# MaxBoard.net
KiCad netlist of a schematic drawn in EAGLE
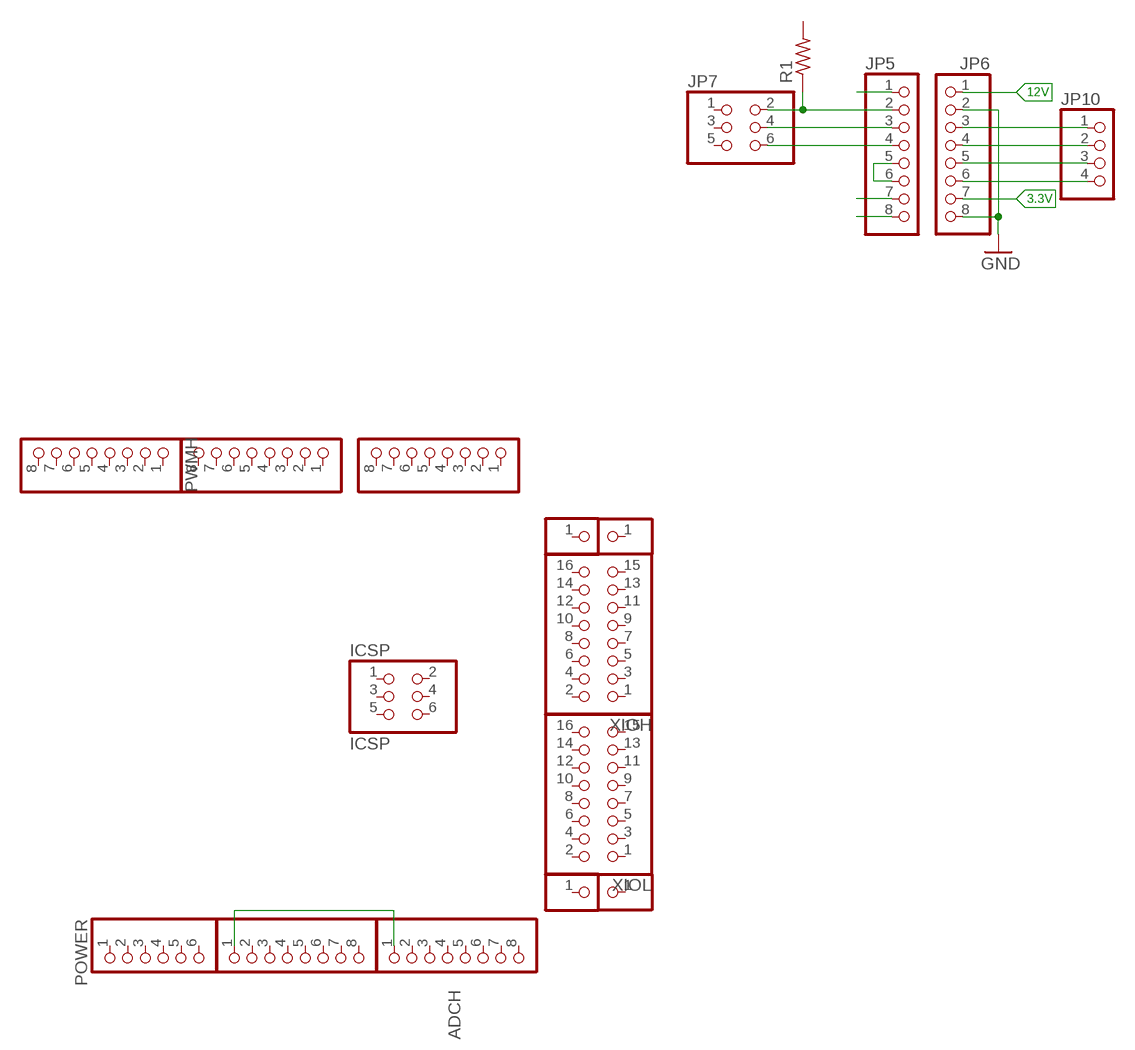
[diagram p0: schematic, sheet 1]

(export (version "E")
  (design (tool "Eeschema 10.0.6"))
  (components
    (comp (ref "ADCH")
      (value "PINHD-1X8")
      (footprint "eagle-import:1X08")
      (libsource (lib "eagle-import") (part "PINHD-1X8"))
    )
    (comp (ref "ADCL")
      (value "PINHD-1X8")
      (footprint "eagle-import:1X08")
      (libsource (lib "eagle-import") (part "PINHD-1X8"))
    )
    (comp (ref "COMMUNICATION")
      (value "PINHD-1X8")
      (footprint "eagle-import:1X08")
      (libsource (lib "eagle-import") (part "PINHD-1X8"))
    )
    (comp (ref "ICSP")
      (value "ICSP")
      (footprint "eagle-import:2X03")
      (libsource (lib "eagle-import") (part "PINHD-2X3"))
    )
    (comp (ref "JP1")
      (value "PINHD-1X1")
      (footprint "eagle-import:1X01")
      (libsource (lib "eagle-import") (part "PINHD-1X1"))
    )
    (comp (ref "JP2")
      (value "PINHD-1X1")
      (footprint "eagle-import:1X01")
      (libsource (lib "eagle-import") (part "PINHD-1X1"))
    )
    (comp (ref "JP3")
      (value "PINHD-1X1")
      (footprint "eagle-import:1X01")
      (libsource (lib "eagle-import") (part "PINHD-1X1"))
    )
    (comp (ref "JP4")
      (value "PINHD-1X1")
      (footprint "eagle-import:1X01")
      (libsource (lib "eagle-import") (part "PINHD-1X1"))
    )
    (comp (ref "JP5")
      (value "PINHD-1X8")
      (footprint "eagle-import:1X08")
      (libsource (lib "eagle-import") (part "PINHD-1X8"))
    )
    (comp (ref "JP6")
      (value "PINHD-1X8")
      (footprint "eagle-import:1X08")
      (libsource (lib "eagle-import") (part "PINHD-1X8"))
    )
    (comp (ref "JP7")
      (value "PINHD-2X3")
      (footprint "eagle-import:2X03")
      (libsource (lib "eagle-import") (part "PINHD-2X3"))
    )
    (comp (ref "JP10")
      (value "PINHD-1X4")
      (footprint "eagle-import:1X04")
      (libsource (lib "eagle-import") (part "PINHD-1X4"))
    )
    (comp (ref "POWER")
      (value "PINHD-1X6")
      (footprint "eagle-import:1X06")
      (libsource (lib "eagle-import") (part "PINHD-1X6"))
    )
    (comp (ref "PWMH")
      (value "PINHD-1X8")
      (footprint "eagle-import:1X08")
      (libsource (lib "eagle-import") (part "PINHD-1X8"))
    )
    (comp (ref "PWML")
      (value "PINHD-1X8")
      (footprint "eagle-import:1X08")
      (libsource (lib "eagle-import") (part "PINHD-1X8"))
    )
    (comp (ref "R1")
      (value "R-US_0207/7")
      (footprint "eagle-import:0207_7")
      (libsource (lib "eagle-import") (part "R-US_0207/7"))
    )
    (comp (ref "XIOH")
      (value "PINHD-2X8")
      (footprint "eagle-import:2X08")
      (libsource (lib "eagle-import") (part "PINHD-2X8"))
    )
    (comp (ref "XIOL")
      (value "PINHD-2X8")
      (footprint "eagle-import:2X08")
      (libsource (lib "eagle-import") (part "PINHD-2X8"))
    )
  )
  (nets
    (net (code "1") (name "3.3V") (class "Default")
      (node (ref "JP6") (pin "7") (pinfunction "7_7") (pintype "passive"))
    )
    (net (code "2") (name "12V") (class "Default")
      (node (ref "JP6") (pin "1") (pinfunction "1_1") (pintype "passive"))
    )
    (net (code "3") (name "GND") (class "Default")
      (node (ref "JP6") (pin "2") (pinfunction "2_2") (pintype "passive"))
      (node (ref "JP6") (pin "8") (pinfunction "8_8") (pintype "passive"))
    )
    (net (code "4") (name "Net-(ADCH-Pad1)") (class "Default")
      (node (ref "ADCH") (pin "1") (pinfunction "1_1") (pintype "passive"))
      (node (ref "ADCL") (pin "1") (pinfunction "1_1") (pintype "passive"))
    )
    (net (code "5") (name "Net-(JP5-Pad2)") (class "Default")
      (node (ref "JP5") (pin "2") (pinfunction "2_2") (pintype "passive"))
      (node (ref "JP7") (pin "2") (pinfunction "2_2") (pintype "passive"))
      (node (ref "R1") (pin "1") (pinfunction "1_1") (pintype "passive"))
    )
    (net (code "6") (name "Net-(JP5-Pad3)") (class "Default")
      (node (ref "JP5") (pin "3") (pinfunction "3_3") (pintype "passive"))
      (node (ref "JP7") (pin "4") (pinfunction "4_4") (pintype "passive"))
    )
    (net (code "7") (name "Net-(JP5-Pad4)") (class "Default")
      (node (ref "JP5") (pin "4") (pinfunction "4_4") (pintype "passive"))
      (node (ref "JP7") (pin "6") (pinfunction "6_6") (pintype "passive"))
    )
    (net (code "8") (name "Net-(JP5-Pad5)") (class "Default")
      (node (ref "JP5") (pin "5") (pinfunction "5_5") (pintype "passive"))
      (node (ref "JP5") (pin "6") (pinfunction "6_6") (pintype "passive"))
    )
    (net (code "9") (name "Net-(JP10-Pad1)") (class "Default")
      (node (ref "JP10") (pin "1") (pinfunction "1_1") (pintype "passive"))
      (node (ref "JP6") (pin "3") (pinfunction "3_3") (pintype "passive"))
    )
    (net (code "10") (name "Net-(JP10-Pad2)") (class "Default")
      (node (ref "JP10") (pin "2") (pinfunction "2_2") (pintype "passive"))
      (node (ref "JP6") (pin "4") (pinfunction "4_4") (pintype "passive"))
    )
    (net (code "11") (name "Net-(JP10-Pad3)") (class "Default")
      (node (ref "JP10") (pin "3") (pinfunction "3_3") (pintype "passive"))
      (node (ref "JP6") (pin "5") (pinfunction "5_5") (pintype "passive"))
    )
    (net (code "12") (name "Net-(JP10-Pad4)") (class "Default")
      (node (ref "JP10") (pin "4") (pinfunction "4_4") (pintype "passive"))
      (node (ref "JP6") (pin "6") (pinfunction "6_6") (pintype "passive"))
    )
    (net (code "13") (name "unconnected-(ADCH-Pad2)") (class "Default")
      (node (ref "ADCH") (pin "2") (pinfunction "2_2") (pintype "passive"))
    )
    (net (code "14") (name "unconnected-(ADCH-Pad3)") (class "Default")
      (node (ref "ADCH") (pin "3") (pinfunction "3_3") (pintype "passive"))
    )
    (net (code "15") (name "unconnected-(ADCH-Pad4)") (class "Default")
      (node (ref "ADCH") (pin "4") (pinfunction "4_4") (pintype "passive"))
    )
    (net (code "16") (name "unconnected-(ADCH-Pad5)") (class "Default")
      (node (ref "ADCH") (pin "5") (pinfunction "5_5") (pintype "passive"))
    )
    (net (code "17") (name "unconnected-(ADCH-Pad6)") (class "Default")
      (node (ref "ADCH") (pin "6") (pinfunction "6_6") (pintype "passive"))
    )
    (net (code "18") (name "unconnected-(ADCH-Pad7)") (class "Default")
      (node (ref "ADCH") (pin "7") (pinfunction "7_7") (pintype "passive"))
    )
    (net (code "19") (name "unconnected-(ADCH-Pad8)") (class "Default")
      (node (ref "ADCH") (pin "8") (pinfunction "8_8") (pintype "passive"))
    )
    (net (code "20") (name "unconnected-(ADCL-Pad2)") (class "Default")
      (node (ref "ADCL") (pin "2") (pinfunction "2_2") (pintype "passive"))
    )
    (net (code "21") (name "unconnected-(ADCL-Pad3)") (class "Default")
      (node (ref "ADCL") (pin "3") (pinfunction "3_3") (pintype "passive"))
    )
    (net (code "22") (name "unconnected-(ADCL-Pad4)") (class "Default")
      (node (ref "ADCL") (pin "4") (pinfunction "4_4") (pintype "passive"))
    )
    (net (code "23") (name "unconnected-(ADCL-Pad5)") (class "Default")
      (node (ref "ADCL") (pin "5") (pinfunction "5_5") (pintype "passive"))
    )
    (net (code "24") (name "unconnected-(ADCL-Pad6)") (class "Default")
      (node (ref "ADCL") (pin "6") (pinfunction "6_6") (pintype "passive"))
    )
    (net (code "25") (name "unconnected-(ADCL-Pad7)") (class "Default")
      (node (ref "ADCL") (pin "7") (pinfunction "7_7") (pintype "passive"))
    )
    (net (code "26") (name "unconnected-(ADCL-Pad8)") (class "Default")
      (node (ref "ADCL") (pin "8") (pinfunction "8_8") (pintype "passive"))
    )
    (net (code "27") (name "unconnected-(COMMUNICATION-Pad1)") (class "Default")
      (node (ref "COMMUNICATION") (pin "1") (pinfunction "1_1") (pintype "passive"))
    )
    (net (code "28") (name "unconnected-(COMMUNICATION-Pad2)") (class "Default")
      (node (ref "COMMUNICATION") (pin "2") (pinfunction "2_2") (pintype "passive"))
    )
    (net (code "29") (name "unconnected-(COMMUNICATION-Pad3)") (class "Default")
      (node (ref "COMMUNICATION") (pin "3") (pinfunction "3_3") (pintype "passive"))
    )
    (net (code "30") (name "unconnected-(COMMUNICATION-Pad4)") (class "Default")
      (node (ref "COMMUNICATION") (pin "4") (pinfunction "4_4") (pintype "passive"))
    )
    (net (code "31") (name "unconnected-(COMMUNICATION-Pad5)") (class "Default")
      (node (ref "COMMUNICATION") (pin "5") (pinfunction "5_5") (pintype "passive"))
    )
    (net (code "32") (name "unconnected-(COMMUNICATION-Pad6)") (class "Default")
      (node (ref "COMMUNICATION") (pin "6") (pinfunction "6_6") (pintype "passive"))
    )
    (net (code "33") (name "unconnected-(COMMUNICATION-Pad7)") (class "Default")
      (node (ref "COMMUNICATION") (pin "7") (pinfunction "7_7") (pintype "passive"))
    )
    (net (code "34") (name "unconnected-(COMMUNICATION-Pad8)") (class "Default")
      (node (ref "COMMUNICATION") (pin "8") (pinfunction "8_8") (pintype "passive"))
    )
    (net (code "35") (name "unconnected-(ICSP-Pad1)") (class "Default")
      (node (ref "ICSP") (pin "1") (pinfunction "1_1") (pintype "passive"))
    )
    (net (code "36") (name "unconnected-(ICSP-Pad2)") (class "Default")
      (node (ref "ICSP") (pin "2") (pinfunction "2_2") (pintype "passive"))
    )
    (net (code "37") (name "unconnected-(ICSP-Pad3)") (class "Default")
      (node (ref "ICSP") (pin "3") (pinfunction "3_3") (pintype "passive"))
    )
    (net (code "38") (name "unconnected-(ICSP-Pad4)") (class "Default")
      (node (ref "ICSP") (pin "4") (pinfunction "4_4") (pintype "passive"))
    )
    (net (code "39") (name "unconnected-(ICSP-Pad5)") (class "Default")
      (node (ref "ICSP") (pin "5") (pinfunction "5_5") (pintype "passive"))
    )
    (net (code "40") (name "unconnected-(ICSP-Pad6)") (class "Default")
      (node (ref "ICSP") (pin "6") (pinfunction "6_6") (pintype "passive"))
    )
    (net (code "41") (name "unconnected-(JP1-Pad1)") (class "Default")
      (node (ref "JP1") (pin "1") (pinfunction "1_1") (pintype "passive"))
    )
    (net (code "42") (name "unconnected-(JP2-Pad1)") (class "Default")
      (node (ref "JP2") (pin "1") (pinfunction "1_1") (pintype "passive"))
    )
    (net (code "43") (name "unconnected-(JP3-Pad1)") (class "Default")
      (node (ref "JP3") (pin "1") (pinfunction "1_1") (pintype "passive"))
    )
    (net (code "44") (name "unconnected-(JP4-Pad1)") (class "Default")
      (node (ref "JP4") (pin "1") (pinfunction "1_1") (pintype "passive"))
    )
    (net (code "45") (name "unconnected-(JP5-Pad1)") (class "Default")
      (node (ref "JP5") (pin "1") (pinfunction "1_1") (pintype "passive"))
    )
    (net (code "46") (name "unconnected-(JP5-Pad7)") (class "Default")
      (node (ref "JP5") (pin "7") (pinfunction "7_7") (pintype "passive"))
    )
    (net (code "47") (name "unconnected-(JP5-Pad8)") (class "Default")
      (node (ref "JP5") (pin "8") (pinfunction "8_8") (pintype "passive"))
    )
    (net (code "48") (name "unconnected-(JP7-Pad1)") (class "Default")
      (node (ref "JP7") (pin "1") (pinfunction "1_1") (pintype "passive"))
    )
    (net (code "49") (name "unconnected-(JP7-Pad3)") (class "Default")
      (node (ref "JP7") (pin "3") (pinfunction "3_3") (pintype "passive"))
    )
    (net (code "50") (name "unconnected-(JP7-Pad5)") (class "Default")
      (node (ref "JP7") (pin "5") (pinfunction "5_5") (pintype "passive"))
    )
    (net (code "51") (name "unconnected-(POWER-Pad1)") (class "Default")
      (node (ref "POWER") (pin "1") (pinfunction "1_1") (pintype "passive"))
    )
    (net (code "52") (name "unconnected-(POWER-Pad2)") (class "Default")
      (node (ref "POWER") (pin "2") (pinfunction "2_2") (pintype "passive"))
    )
    (net (code "53") (name "unconnected-(POWER-Pad3)") (class "Default")
      (node (ref "POWER") (pin "3") (pinfunction "3_3") (pintype "passive"))
    )
    (net (code "54") (name "unconnected-(POWER-Pad4)") (class "Default")
      (node (ref "POWER") (pin "4") (pinfunction "4_4") (pintype "passive"))
    )
    (net (code "55") (name "unconnected-(POWER-Pad5)") (class "Default")
      (node (ref "POWER") (pin "5") (pinfunction "5_5") (pintype "passive"))
    )
    (net (code "56") (name "unconnected-(POWER-Pad6)") (class "Default")
      (node (ref "POWER") (pin "6") (pinfunction "6_6") (pintype "passive"))
    )
    (net (code "57") (name "unconnected-(PWMH-Pad1)") (class "Default")
      (node (ref "PWMH") (pin "1") (pinfunction "1_1") (pintype "passive"))
    )
    (net (code "58") (name "unconnected-(PWMH-Pad2)") (class "Default")
      (node (ref "PWMH") (pin "2") (pinfunction "2_2") (pintype "passive"))
    )
    (net (code "59") (name "unconnected-(PWMH-Pad3)") (class "Default")
      (node (ref "PWMH") (pin "3") (pinfunction "3_3") (pintype "passive"))
    )
    (net (code "60") (name "unconnected-(PWMH-Pad4)") (class "Default")
      (node (ref "PWMH") (pin "4") (pinfunction "4_4") (pintype "passive"))
    )
    (net (code "61") (name "unconnected-(PWMH-Pad5)") (class "Default")
      (node (ref "PWMH") (pin "5") (pinfunction "5_5") (pintype "passive"))
    )
    (net (code "62") (name "unconnected-(PWMH-Pad6)") (class "Default")
      (node (ref "PWMH") (pin "6") (pinfunction "6_6") (pintype "passive"))
    )
    (net (code "63") (name "unconnected-(PWMH-Pad7)") (class "Default")
      (node (ref "PWMH") (pin "7") (pinfunction "7_7") (pintype "passive"))
    )
    (net (code "64") (name "unconnected-(PWMH-Pad8)") (class "Default")
      (node (ref "PWMH") (pin "8") (pinfunction "8_8") (pintype "passive"))
    )
    (net (code "65") (name "unconnected-(PWML-Pad1)") (class "Default")
      (node (ref "PWML") (pin "1") (pinfunction "1_1") (pintype "passive"))
    )
    (net (code "66") (name "unconnected-(PWML-Pad2)") (class "Default")
      (node (ref "PWML") (pin "2") (pinfunction "2_2") (pintype "passive"))
    )
    (net (code "67") (name "unconnected-(PWML-Pad3)") (class "Default")
      (node (ref "PWML") (pin "3") (pinfunction "3_3") (pintype "passive"))
    )
    (net (code "68") (name "unconnected-(PWML-Pad4)") (class "Default")
      (node (ref "PWML") (pin "4") (pinfunction "4_4") (pintype "passive"))
    )
    (net (code "69") (name "unconnected-(PWML-Pad5)") (class "Default")
      (node (ref "PWML") (pin "5") (pinfunction "5_5") (pintype "passive"))
    )
    (net (code "70") (name "unconnected-(PWML-Pad6)") (class "Default")
      (node (ref "PWML") (pin "6") (pinfunction "6_6") (pintype "passive"))
    )
    (net (code "71") (name "unconnected-(PWML-Pad7)") (class "Default")
      (node (ref "PWML") (pin "7") (pinfunction "7_7") (pintype "passive"))
    )
    (net (code "72") (name "unconnected-(PWML-Pad8)") (class "Default")
      (node (ref "PWML") (pin "8") (pinfunction "8_8") (pintype "passive"))
    )
    (net (code "73") (name "unconnected-(R1-Pad2)") (class "Default")
      (node (ref "R1") (pin "2") (pinfunction "2_2") (pintype "passive"))
    )
    (net (code "74") (name "unconnected-(XIOH-Pad1)") (class "Default")
      (node (ref "XIOH") (pin "1") (pinfunction "1_1") (pintype "passive"))
    )
    (net (code "75") (name "unconnected-(XIOH-Pad2)") (class "Default")
      (node (ref "XIOH") (pin "2") (pinfunction "2_2") (pintype "passive"))
    )
    (net (code "76") (name "unconnected-(XIOH-Pad3)") (class "Default")
      (node (ref "XIOH") (pin "3") (pinfunction "3_3") (pintype "passive"))
    )
    (net (code "77") (name "unconnected-(XIOH-Pad4)") (class "Default")
      (node (ref "XIOH") (pin "4") (pinfunction "4_4") (pintype "passive"))
    )
    (net (code "78") (name "unconnected-(XIOH-Pad5)") (class "Default")
      (node (ref "XIOH") (pin "5") (pinfunction "5_5") (pintype "passive"))
    )
    (net (code "79") (name "unconnected-(XIOH-Pad6)") (class "Default")
      (node (ref "XIOH") (pin "6") (pinfunction "6_6") (pintype "passive"))
    )
    (net (code "80") (name "unconnected-(XIOH-Pad7)") (class "Default")
      (node (ref "XIOH") (pin "7") (pinfunction "7_7") (pintype "passive"))
    )
    (net (code "81") (name "unconnected-(XIOH-Pad8)") (class "Default")
      (node (ref "XIOH") (pin "8") (pinfunction "8_8") (pintype "passive"))
    )
    (net (code "82") (name "unconnected-(XIOH-Pad9)") (class "Default")
      (node (ref "XIOH") (pin "9") (pinfunction "9_9") (pintype "passive"))
    )
    (net (code "83") (name "unconnected-(XIOH-Pad10)") (class "Default")
      (node (ref "XIOH") (pin "10") (pinfunction "10_10") (pintype "passive"))
    )
    (net (code "84") (name "unconnected-(XIOH-Pad11)") (class "Default")
      (node (ref "XIOH") (pin "11") (pinfunction "11_11") (pintype "passive"))
    )
    (net (code "85") (name "unconnected-(XIOH-Pad12)") (class "Default")
      (node (ref "XIOH") (pin "12") (pinfunction "12_12") (pintype "passive"))
    )
    (net (code "86") (name "unconnected-(XIOH-Pad13)") (class "Default")
      (node (ref "XIOH") (pin "13") (pinfunction "13_13") (pintype "passive"))
    )
    (net (code "87") (name "unconnected-(XIOH-Pad14)") (class "Default")
      (node (ref "XIOH") (pin "14") (pinfunction "14_14") (pintype "passive"))
    )
    (net (code "88") (name "unconnected-(XIOH-Pad15)") (class "Default")
      (node (ref "XIOH") (pin "15") (pinfunction "15_15") (pintype "passive"))
    )
    (net (code "89") (name "unconnected-(XIOH-Pad16)") (class "Default")
      (node (ref "XIOH") (pin "16") (pinfunction "16_16") (pintype "passive"))
    )
    (net (code "90") (name "unconnected-(XIOL-Pad1)") (class "Default")
      (node (ref "XIOL") (pin "1") (pinfunction "1_1") (pintype "passive"))
    )
    (net (code "91") (name "unconnected-(XIOL-Pad2)") (class "Default")
      (node (ref "XIOL") (pin "2") (pinfunction "2_2") (pintype "passive"))
    )
    (net (code "92") (name "unconnected-(XIOL-Pad3)") (class "Default")
      (node (ref "XIOL") (pin "3") (pinfunction "3_3") (pintype "passive"))
    )
    (net (code "93") (name "unconnected-(XIOL-Pad4)") (class "Default")
      (node (ref "XIOL") (pin "4") (pinfunction "4_4") (pintype "passive"))
    )
    (net (code "94") (name "unconnected-(XIOL-Pad5)") (class "Default")
      (node (ref "XIOL") (pin "5") (pinfunction "5_5") (pintype "passive"))
    )
    (net (code "95") (name "unconnected-(XIOL-Pad6)") (class "Default")
      (node (ref "XIOL") (pin "6") (pinfunction "6_6") (pintype "passive"))
    )
    (net (code "96") (name "unconnected-(XIOL-Pad7)") (class "Default")
      (node (ref "XIOL") (pin "7") (pinfunction "7_7") (pintype "passive"))
    )
    (net (code "97") (name "unconnected-(XIOL-Pad8)") (class "Default")
      (node (ref "XIOL") (pin "8") (pinfunction "8_8") (pintype "passive"))
    )
    (net (code "98") (name "unconnected-(XIOL-Pad9)") (class "Default")
      (node (ref "XIOL") (pin "9") (pinfunction "9_9") (pintype "passive"))
    )
    (net (code "99") (name "unconnected-(XIOL-Pad10)") (class "Default")
      (node (ref "XIOL") (pin "10") (pinfunction "10_10") (pintype "passive"))
    )
    (net (code "100") (name "unconnected-(XIOL-Pad11)") (class "Default")
      (node (ref "XIOL") (pin "11") (pinfunction "11_11") (pintype "passive"))
    )
    (net (code "101") (name "unconnected-(XIOL-Pad12)") (class "Default")
      (node (ref "XIOL") (pin "12") (pinfunction "12_12") (pintype "passive"))
    )
    (net (code "102") (name "unconnected-(XIOL-Pad13)") (class "Default")
      (node (ref "XIOL") (pin "13") (pinfunction "13_13") (pintype "passive"))
    )
    (net (code "103") (name "unconnected-(XIOL-Pad14)") (class "Default")
      (node (ref "XIOL") (pin "14") (pinfunction "14_14") (pintype "passive"))
    )
    (net (code "104") (name "unconnected-(XIOL-Pad15)") (class "Default")
      (node (ref "XIOL") (pin "15") (pinfunction "15_15") (pintype "passive"))
    )
    (net (code "105") (name "unconnected-(XIOL-Pad16)") (class "Default")
      (node (ref "XIOL") (pin "16") (pinfunction "16_16") (pintype "passive"))
    )
  )
)
